# Relay_Interface.net
KiCad netlist of a schematic drawn in Altium Designer
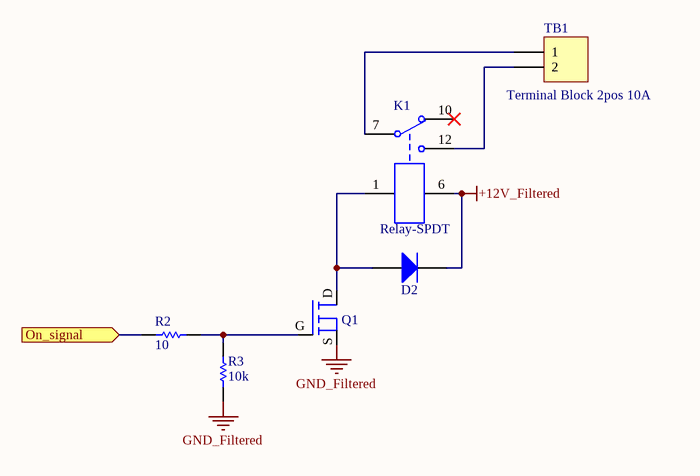
[diagram p0: Relay_Interface.SchDoc]

(export (version "E")
  (design (tool "Eeschema 10.0.6"))
  (components
    (comp (ref "D2")
      (value "Diode GEN PURP")
      (footprint "SOT-23")
      (description "DIODE GEN PURP 100V 200MA SOT23")
      (libsource (lib "Componentes_SOC") (part "Diode GEN PURP"))
    )
    (comp (ref "K1")
      (value "Relay-SPDT")
      (footprint "RELAY_SPDT")
      (description "Relay SPDT 12V Coil")
      (libsource (lib "Componentes_SOC") (part "Relay-SPDT"))
    )
    (comp (ref "Q1")
      (value "MOSFET N")
      (footprint "Footprints_SOC:SOT23_MOD")
      (description "2N7002-FDICT-ND")
      (libsource (lib "Componentes_SOC") (part "MOSFET_N"))
    )
    (comp (ref "R2") (value "10") (footprint "RES_0603") (libsource (lib "Componentes_SOC") (part "Res0603")))
    (comp (ref "R3")
      (value "10k")
      (footprint "RES_0603")
      (libsource (lib "Componentes_SOC") (part "Res0603"))
    )
    (comp (ref "TB1")
      (value "Terminal Block 2pos 10A")
      (footprint "Terminal Block 2 pos 8A")
      (description "Wurth Electronics Inc.")
      (libsource (lib "Componentes_SOC") (part "Terminal Block 2 pos 8A pitch 5mm"))
    )
  )
  (nets
    (net (code "1") (name "+12V_Filtered") (class "Default")
      (node (ref "D2") (pin "3") (pinfunction "K_3") (pintype "passive"))
      (node (ref "K1") (pin "6") (pintype "passive"))
    )
    (net (code "2") (name "/On_signal") (class "Default")
      (node (ref "R2") (pin "1") (pinfunction "1_1") (pintype "passive"))
    )
    (net (code "3") (name "GND_Filtered") (class "Default")
      (node (ref "Q1") (pin "S") (pinfunction "S_S") (pintype "passive"))
      (node (ref "R3") (pin "2") (pinfunction "2_2") (pintype "passive"))
    )
    (net (code "4") (name "Net-(D2-A)") (class "Default")
      (node (ref "D2") (pin "1") (pinfunction "A_1") (pintype "passive"))
      (node (ref "K1") (pin "1") (pintype "passive"))
      (node (ref "Q1") (pin "D") (pinfunction "D_D") (pintype "passive"))
    )
    (net (code "5") (name "Net-(K1-COM)") (class "Default")
      (node (ref "K1") (pin "7") (pinfunction "COM_7") (pintype "passive"))
      (node (ref "TB1") (pin "1") (pinfunction "1_1") (pintype "passive"))
    )
    (net (code "6") (name "Net-(K1-NO)") (class "Default")
      (node (ref "K1") (pin "12") (pinfunction "NO_12") (pintype "passive"))
      (node (ref "TB1") (pin "2") (pinfunction "2_2") (pintype "passive"))
    )
    (net (code "7") (name "Net-(Q1-PadG)") (class "Default")
      (node (ref "Q1") (pin "G") (pinfunction "G_G") (pintype "passive"))
      (node (ref "R2") (pin "2") (pinfunction "2_2") (pintype "passive"))
      (node (ref "R3") (pin "1") (pinfunction "1_1") (pintype "passive"))
    )
    (net (code "8") (name "unconnected-(D2-NC-Pad2)") (class "Default")
      (node (ref "D2") (pin "2") (pinfunction "NC_2") (pintype "passive"))
    )
    (net (code "9") (name "unconnected-(K1-NC-Pad10)") (class "Default")
      (node (ref "K1") (pin "10") (pinfunction "NC_10") (pintype "passive+no_connect"))
    )
  )
)
